# design.net
KiCad netlist of a schematic drawn in Altium Designer
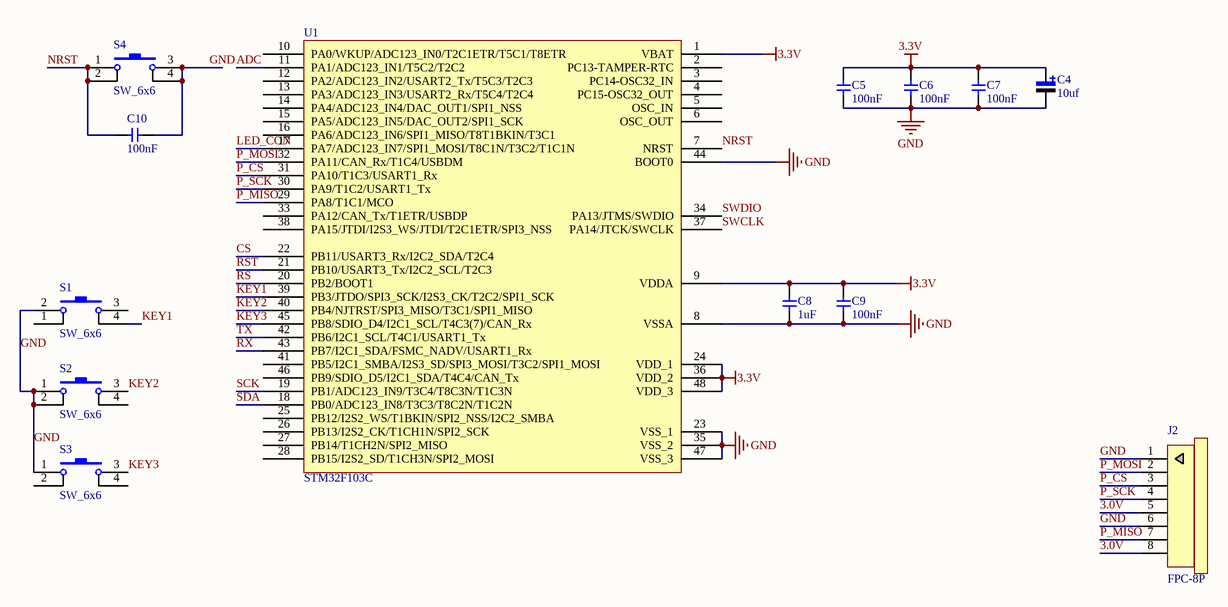
[diagram p0: 主控.SchDoc]

(export (version "E")
  (design (tool "Eeschema 10.0.6"))
  (components
    (comp (ref "C4")
      (value "10uf")
      (footprint "CAP-3216")
      (description "极性电解电容")
      (fields (field (name "Comment") "Cap Pol") (field (name "PUBLISHER") "Altium Limited"))
      (libsource (lib "fszhang") (part "Cap Pol"))
    )
    (comp (ref "C5")
      (value "100nF")
      (footprint "0603-2")
      (description "无极性电容")
      (fields (field (name "Comment") "Cap") (field (name "PUBLISHER") "Altium Limited"))
      (libsource (lib "fszhang") (part "Cap"))
    )
    (comp (ref "C6")
      (value "100nF")
      (footprint "0603-2")
      (description "无极性电容")
      (fields (field (name "Comment") "Cap") (field (name "PUBLISHER") "Altium Limited"))
      (libsource (lib "fszhang") (part "Cap"))
    )
    (comp (ref "C7")
      (value "100nF")
      (footprint "0603-2")
      (description "无极性电容")
      (fields (field (name "Comment") "Cap") (field (name "PUBLISHER") "Altium Limited"))
      (libsource (lib "fszhang") (part "Cap"))
    )
    (comp (ref "C8")
      (value "1uF")
      (footprint "0603-2")
      (description "无极性电容")
      (fields (field (name "Comment") "Cap") (field (name "PUBLISHER") "Altium Limited"))
      (libsource (lib "fszhang") (part "Cap"))
    )
    (comp (ref "C9")
      (value "100nF")
      (footprint "0603-2")
      (description "无极性电容")
      (fields (field (name "Comment") "Cap") (field (name "PUBLISHER") "Altium Limited"))
      (libsource (lib "fszhang") (part "Cap"))
    )
    (comp (ref "C10")
      (value "100nF")
      (footprint "0805-2")
      (description "无极性电容")
      (fields (field (name "Comment") "Cap") (field (name "PUBLISHER") "Altium Limited"))
      (libsource (lib "fszhang") (part "Cap"))
    )
    (comp (ref "J2")
      (value "FPC-8P")
      (footprint "FPC0.5-8P-C")
      (description "FPC排线连接器")
      (libsource (lib "fszhang") (part "FPC-8P"))
    )
    (comp (ref "S1")
      (value "SW_6x6")
      (footprint "button_6x6")
      (description "轻触开关")
      (libsource (lib "") (part "button_6x6_1"))
    )
    (comp (ref "S2")
      (value "SW_6x6")
      (footprint "button_6x6")
      (description "轻触开关")
      (libsource (lib "fszhang") (part "button_6x6"))
    )
    (comp (ref "S3")
      (value "SW_6x6")
      (footprint "button_6x6")
      (description "轻触开关")
      (libsource (lib "fszhang") (part "button_6x6"))
    )
    (comp (ref "S4")
      (value "SW_6x6")
      (footprint "button_6x6")
      (description "轻触开关")
      (libsource (lib "fszhang") (part "button_6x6"))
    )
    (comp (ref "U1")
      (value "STM32F103C")
      (footprint "LQFP-48_M")
      (description "STM32单片机48引脚")
      (libsource (lib "fszhang") (part "STM32F103C"))
    )
  )
  (nets
    (net (code "1") (name "/3.0V") (class "Default")
      (node (ref "J2") (pin "5") (pinfunction "5_5") (pintype "passive"))
      (node (ref "J2") (pin "8") (pinfunction "8_8") (pintype "passive"))
    )
    (net (code "2") (name "/ADC") (class "Default")
      (node (ref "U1") (pin "11") (pinfunction "PA1/ADC123_IN1/T5C2/T2C2_11") (pintype "passive"))
    )
    (net (code "3") (name "/CS") (class "Default")
      (node (ref "U1") (pin "22") (pinfunction "PB11/USART3_Rx/I2C2_SDA/T2C4_22") (pintype "passive"))
    )
    (net (code "4") (name "/KEY1") (class "Default")
      (node (ref "S1") (pin "4") (pinfunction "4_4") (pintype "passive"))
      (node (ref "U1") (pin "39") (pinfunction "PB3/JTDO/SPI3_SCK/I2S3_CK/T2C2/SPI1_SCK_39") (pintype "passive"))
    )
    (net (code "5") (name "/KEY2") (class "Default")
      (node (ref "S2") (pin "3") (pinfunction "3_3") (pintype "passive"))
      (node (ref "U1") (pin "40") (pinfunction "PB4/NJTRST/SPI3_MISO/T3C1/SPI1_MISO_40") (pintype "passive"))
    )
    (net (code "6") (name "/KEY3") (class "Default")
      (node (ref "S3") (pin "3") (pinfunction "3_3") (pintype "passive"))
      (node (ref "U1") (pin "45") (pinfunction "PB8/SDIO_D4/I2C1_SCL/T4C3(7)/CAN_Rx_45") (pintype "passive"))
    )
    (net (code "7") (name "/LED_CON") (class "Default")
      (node (ref "U1") (pin "17") (pinfunction "PA7/ADC123_IN7/SPI1_MOSI/T8C1N/T3C2/T1C1N_17") (pintype "passive"))
    )
    (net (code "8") (name "/NRST") (class "Default")
      (node (ref "C10") (pin "1") (pinfunction "1_1") (pintype "passive"))
      (node (ref "S4") (pin "1") (pinfunction "1_1") (pintype "passive"))
      (node (ref "S4") (pin "2") (pinfunction "2_2") (pintype "passive"))
      (node (ref "U1") (pin "7") (pinfunction "NRST_7") (pintype "passive"))
    )
    (net (code "9") (name "/P_CS") (class "Default")
      (node (ref "J2") (pin "3") (pinfunction "3_3") (pintype "passive"))
      (node (ref "U1") (pin "31") (pinfunction "PA10/T1C3/USART1_Rx_31") (pintype "passive"))
    )
    (net (code "10") (name "/P_MISO") (class "Default")
      (node (ref "J2") (pin "7") (pinfunction "7_7") (pintype "passive"))
      (node (ref "U1") (pin "29") (pinfunction "PA8/T1C1/MCO_29") (pintype "passive"))
    )
    (net (code "11") (name "/P_MOSI") (class "Default")
      (node (ref "J2") (pin "2") (pinfunction "2_2") (pintype "passive"))
      (node (ref "U1") (pin "32") (pinfunction "PA11/CAN_Rx/T1C4/USBDM_32") (pintype "passive"))
    )
    (net (code "12") (name "/P_SCK") (class "Default")
      (node (ref "J2") (pin "4") (pinfunction "4_4") (pintype "passive"))
      (node (ref "U1") (pin "30") (pinfunction "PA9/T1C2/USART1_Tx_30") (pintype "passive"))
    )
    (net (code "13") (name "/RS") (class "Default")
      (node (ref "U1") (pin "20") (pinfunction "PB2/BOOT1_20") (pintype "passive"))
    )
    (net (code "14") (name "/RST") (class "Default")
      (node (ref "U1") (pin "21") (pinfunction "PB10/USART3_Tx/I2C2_SCL/T2C3_21") (pintype "passive"))
    )
    (net (code "15") (name "/RX") (class "Default")
      (node (ref "U1") (pin "43") (pinfunction "PB7/I2C1_SDA/FSMC_NADV/USART1_Rx_43") (pintype "passive"))
    )
    (net (code "16") (name "/SCK") (class "Default")
      (node (ref "U1") (pin "19") (pinfunction "PB1/ADC123_IN9/T3C4/T8C3N/T1C3N_19") (pintype "passive"))
    )
    (net (code "17") (name "/SDA") (class "Default")
      (node (ref "U1") (pin "18") (pinfunction "PB0/ADC123_IN8/T3C3/T8C2N/T1C2N_18") (pintype "passive"))
    )
    (net (code "18") (name "/SWCLK") (class "Default")
      (node (ref "U1") (pin "37") (pinfunction "PA14/JTCK/SWCLK_37") (pintype "passive"))
    )
    (net (code "19") (name "/SWDIO") (class "Default")
      (node (ref "U1") (pin "34") (pinfunction "PA13/JTMS/SWDIO_34") (pintype "passive"))
    )
    (net (code "20") (name "/TX") (class "Default")
      (node (ref "U1") (pin "42") (pinfunction "PB6/I2C1_SCL/T4C1/USART1_Tx_42") (pintype "passive"))
    )
    (net (code "21") (name "3.3V") (class "Default")
      (node (ref "C4") (pin "1") (pinfunction "1_1") (pintype "passive"))
      (node (ref "C5") (pin "1") (pinfunction "1_1") (pintype "passive"))
      (node (ref "C6") (pin "1") (pinfunction "1_1") (pintype "passive"))
      (node (ref "C7") (pin "1") (pinfunction "1_1") (pintype "passive"))
      (node (ref "C8") (pin "2") (pinfunction "2_2") (pintype "passive"))
      (node (ref "C9") (pin "2") (pinfunction "2_2") (pintype "passive"))
      (node (ref "U1") (pin "1") (pinfunction "VBAT_1") (pintype "passive"))
      (node (ref "U1") (pin "24") (pinfunction "VDD_1_24") (pintype "passive"))
      (node (ref "U1") (pin "36") (pinfunction "VDD_2_36") (pintype "passive"))
      (node (ref "U1") (pin "48") (pinfunction "VDD_3_48") (pintype "passive"))
      (node (ref "U1") (pin "9") (pinfunction "VDDA_9") (pintype "passive"))
    )
    (net (code "22") (name "GND") (class "Default")
      (node (ref "C10") (pin "2") (pinfunction "2_2") (pintype "passive"))
      (node (ref "C4") (pin "2") (pinfunction "2_2") (pintype "passive"))
      (node (ref "C5") (pin "2") (pinfunction "2_2") (pintype "passive"))
      (node (ref "C6") (pin "2") (pinfunction "2_2") (pintype "passive"))
      (node (ref "C7") (pin "2") (pinfunction "2_2") (pintype "passive"))
      (node (ref "C8") (pin "1") (pinfunction "1_1") (pintype "passive"))
      (node (ref "C9") (pin "1") (pinfunction "1_1") (pintype "passive"))
      (node (ref "J2") (pin "1") (pinfunction "1_1") (pintype "passive"))
      (node (ref "J2") (pin "6") (pinfunction "6_6") (pintype "passive"))
      (node (ref "S1") (pin "2") (pinfunction "2_2") (pintype "passive"))
      (node (ref "S2") (pin "1") (pinfunction "1_1") (pintype "passive"))
      (node (ref "S2") (pin "2") (pinfunction "2_2") (pintype "passive"))
      (node (ref "S3") (pin "1") (pinfunction "1_1") (pintype "passive"))
      (node (ref "S4") (pin "3") (pinfunction "3_3") (pintype "passive"))
      (node (ref "S4") (pin "4") (pinfunction "4_4") (pintype "passive"))
      (node (ref "U1") (pin "23") (pinfunction "VSS_1_23") (pintype "passive"))
      (node (ref "U1") (pin "35") (pinfunction "VSS_2_35") (pintype "passive"))
      (node (ref "U1") (pin "44") (pinfunction "BOOT0_44") (pintype "passive"))
      (node (ref "U1") (pin "47") (pinfunction "VSS_3_47") (pintype "passive"))
      (node (ref "U1") (pin "8") (pinfunction "VSSA_8") (pintype "passive"))
    )
    (net (code "23") (name "unconnected-(S1-Pad1)") (class "Default")
      (node (ref "S1") (pin "1") (pinfunction "1_1") (pintype "passive"))
    )
    (net (code "24") (name "unconnected-(S1-Pad3)") (class "Default")
      (node (ref "S1") (pin "3") (pinfunction "3_3") (pintype "passive"))
    )
    (net (code "25") (name "unconnected-(S2-Pad4)") (class "Default")
      (node (ref "S2") (pin "4") (pinfunction "4_4") (pintype "passive"))
    )
    (net (code "26") (name "unconnected-(S3-Pad2)") (class "Default")
      (node (ref "S3") (pin "2") (pinfunction "2_2") (pintype "passive"))
    )
    (net (code "27") (name "unconnected-(S3-Pad4)") (class "Default")
      (node (ref "S3") (pin "4") (pinfunction "4_4") (pintype "passive"))
    )
    (net (code "28") (name "unconnected-(U1-OSC_IN-Pad5)") (class "Default")
      (node (ref "U1") (pin "5") (pinfunction "OSC_IN_5") (pintype "passive"))
    )
    (net (code "29") (name "unconnected-(U1-OSC_OUT-Pad6)") (class "Default")
      (node (ref "U1") (pin "6") (pinfunction "OSC_OUT_6") (pintype "passive"))
    )
    (net (code "30") (name "unconnected-(U1-PA0{slash}WKUP{slash}ADC123_IN0{slash}T2C1ETR{slash}T5C1{slash}T8ETR-Pad10)") (class "Default")
      (node (ref "U1") (pin "10") (pinfunction "PA0/WKUP/ADC123_IN0/T2C1ETR/T5C1/T8ETR_10") (pintype "passive"))
    )
    (net (code "31") (name "unconnected-(U1-PA2{slash}ADC123_IN2{slash}USART2_Tx{slash}T5C3{slash}T2C3-Pad12)") (class "Default")
      (node (ref "U1") (pin "12") (pinfunction "PA2/ADC123_IN2/USART2_Tx/T5C3/T2C3_12") (pintype "passive"))
    )
    (net (code "32") (name "unconnected-(U1-PA3{slash}ADC123_IN3{slash}USART2_Rx{slash}T5C4{slash}T2C4-Pad13)") (class "Default")
      (node (ref "U1") (pin "13") (pinfunction "PA3/ADC123_IN3/USART2_Rx/T5C4/T2C4_13") (pintype "passive"))
    )
    (net (code "33") (name "unconnected-(U1-PA4{slash}ADC123_IN4{slash}DAC_OUT1{slash}SPI1_NSS-Pad14)") (class "Default")
      (node (ref "U1") (pin "14") (pinfunction "PA4/ADC123_IN4/DAC_OUT1/SPI1_NSS_14") (pintype "passive"))
    )
    (net (code "34") (name "unconnected-(U1-PA5{slash}ADC123_IN5{slash}DAC_OUT2{slash}SPI1_SCK-Pad15)") (class "Default")
      (node (ref "U1") (pin "15") (pinfunction "PA5/ADC123_IN5/DAC_OUT2/SPI1_SCK_15") (pintype "passive"))
    )
    (net (code "35") (name "unconnected-(U1-PA6{slash}ADC123_IN6{slash}SPI1_MISO{slash}T8T1BKIN{slash}T3C1-Pad16)") (class "Default")
      (node (ref "U1") (pin "16") (pinfunction "PA6/ADC123_IN6/SPI1_MISO/T8T1BKIN/T3C1_16") (pintype "passive"))
    )
    (net (code "36") (name "unconnected-(U1-PA12{slash}CAN_Tx{slash}T1ETR{slash}USBDP-Pad33)") (class "Default")
      (node (ref "U1") (pin "33") (pinfunction "PA12/CAN_Tx/T1ETR/USBDP_33") (pintype "passive"))
    )
    (net (code "37") (name "unconnected-(U1-PA15{slash}JTDI{slash}I2S3_WS{slash}JTDI{slash}T2C1ETR{slash}SPI3_NSS-Pad38)") (class "Default")
      (node (ref "U1") (pin "38") (pinfunction "PA15/JTDI/I2S3_WS/JTDI/T2C1ETR/SPI3_NSS_38") (pintype "passive"))
    )
    (net (code "38") (name "unconnected-(U1-PB5{slash}I2C1_SMBA{slash}I2S3_SD{slash}SPI3_MOSI{slash}T3C2{slash}SPI1_MOSI-Pad41)") (class "Default")
      (node (ref "U1") (pin "41") (pinfunction "PB5/I2C1_SMBA/I2S3_SD/SPI3_MOSI/T3C2/SPI1_MOSI_41") (pintype "passive"))
    )
    (net (code "39") (name "unconnected-(U1-PB9{slash}SDIO_D5{slash}I2C1_SDA{slash}T4C4{slash}CAN_Tx-Pad46)") (class "Default")
      (node (ref "U1") (pin "46") (pinfunction "PB9/SDIO_D5/I2C1_SDA/T4C4/CAN_Tx_46") (pintype "passive"))
    )
    (net (code "40") (name "unconnected-(U1-PB12{slash}I2S2_WS{slash}T1BKIN{slash}SPI2_NSS{slash}I2C2_SMBA-Pad25)") (class "Default")
      (node (ref "U1") (pin "25") (pinfunction "PB12/I2S2_WS/T1BKIN/SPI2_NSS/I2C2_SMBA_25") (pintype "passive"))
    )
    (net (code "41") (name "unconnected-(U1-PB13{slash}I2S2_CK{slash}T1CH1N{slash}SPI2_SCK-Pad26)") (class "Default")
      (node (ref "U1") (pin "26") (pinfunction "PB13/I2S2_CK/T1CH1N/SPI2_SCK_26") (pintype "passive"))
    )
    (net (code "42") (name "unconnected-(U1-PB14{slash}T1CH2N{slash}SPI2_MISO-Pad27)") (class "Default")
      (node (ref "U1") (pin "27") (pinfunction "PB14/T1CH2N/SPI2_MISO_27") (pintype "passive"))
    )
    (net (code "43") (name "unconnected-(U1-PB15{slash}I2S2_SD{slash}T1CH3N{slash}SPI2_MOSI-Pad28)") (class "Default")
      (node (ref "U1") (pin "28") (pinfunction "PB15/I2S2_SD/T1CH3N/SPI2_MOSI_28") (pintype "passive"))
    )
    (net (code "44") (name "unconnected-(U1-PC13-TAMPER-RTC-Pad2)") (class "Default")
      (node (ref "U1") (pin "2") (pinfunction "PC13-TAMPER-RTC_2") (pintype "passive"))
    )
    (net (code "45") (name "unconnected-(U1-PC14-OSC32_IN-Pad3)") (class "Default")
      (node (ref "U1") (pin "3") (pinfunction "PC14-OSC32_IN_3") (pintype "passive"))
    )
    (net (code "46") (name "unconnected-(U1-PC15-OSC32_OUT-Pad4)") (class "Default")
      (node (ref "U1") (pin "4") (pinfunction "PC15-OSC32_OUT_4") (pintype "passive"))
    )
  )
)
